# FabricationSumo.net
KiCad netlist of a schematic drawn in Altium Designer
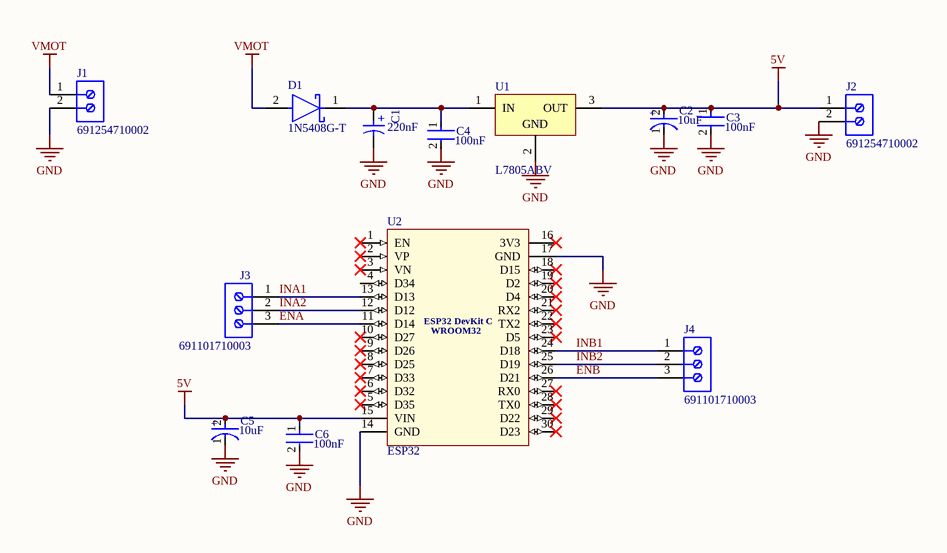
[diagram p0: FabricationSumo.SchDoc]

(export (version "E")
  (design (tool "Eeschema 10.0.6"))
  (components
    (comp (ref "C1")
      (value "860020672002")
      (footprint "WCAP-ATG5_D5H11")
      (description "WCAP-ATG5 Aluminum Electrolytic Capacitors")
      (fields (field (name "TOLERANCE") "20%") (field (name "CAPACITANCE") "220nF"))
      (libsource (lib "Altium Content Vault") (part "Capacitor_Polarized"))
    )
    (comp (ref "C2")
      (value "EEAGA1E100E")
      (footprint "FP-RAD-TH-D_4_0_5-L_7_1-F-MFG")
      (description "Aluminum Electrolytic Capacitors (Radial Lead Type) 10uF ±20% 25V")
      (fields (field (name "CAPACITANCE") "10uF"))
      (libsource (lib "Altium Content Vault") (part "a00bbbee19879c290e62620ae7e47b1"))
    )
    (comp (ref "C3")
      (value "RDED72W104K3K1H03B")
      (footprint "FP-RDE3M1-MFG")
      (description "Ceramic Capacitor 100nF ±10% 450V X7T Radial")
      (fields (field (name "TOLERANCE") "10%") (field (name "CAPACITANCE") "100nF"))
      (libsource (lib "Altium Content Vault") (part "b4654b650e69147ec39a6b967a45e02"))
    )
    (comp (ref "C4")
      (value "RDED72W104K3K1H03B")
      (footprint "FP-RDE3M1-MFG")
      (description "Ceramic Capacitor 100nF ±10% 450V X7T Radial")
      (fields (field (name "TOLERANCE") "10%") (field (name "CAPACITANCE") "100nF"))
      (libsource (lib "Altium Content Vault") (part "b4654b650e69147ec39a6b967a45e02"))
    )
    (comp (ref "C5")
      (value "EEAGA1E100E")
      (footprint "FP-RAD-TH-D_4_0_5-L_7_1-F-MFG")
      (description "Aluminum Electrolytic Capacitors (Radial Lead Type) 10uF ±20% 25V")
      (fields (field (name "CAPACITANCE") "10uF"))
      (libsource (lib "Altium Content Vault") (part "a00bbbee19879c290e62620ae7e47b1"))
    )
    (comp (ref "C6")
      (value "RDED72W104K3K1H03B")
      (footprint "FP-RDE3M1-MFG")
      (description "Ceramic Capacitor 100nF ±10% 450V X7T Radial")
      (fields (field (name "TOLERANCE") "10%") (field (name "CAPACITANCE") "100nF"))
      (libsource (lib "Altium Content Vault") (part "b4654b650e69147ec39a6b967a45e02"))
    )
    (comp (ref "D1")
      (value "1N5408G-T")
      (footprint "FP-DO-201AD-MFG")
      (description "Diode Schottky 40V 1A Through Hole DO-41")
      (fields (field (name "MANUFACTURER") "Diodes Inc."))
      (libsource (lib "Altium Content Vault") (part "1d6ec82d83fb6aee721767c19dac4b9"))
    )
    (comp (ref "J1")
      (value "691254710002")
      (footprint "691254710002")
      (description "Terminal Block, 5MM Pitch, Horizontal, Rising Cage Clamp, 16-30 AWG, 2 Pin")
      (libsource (lib "Altium Content Vault") (part "TBL - 1R - 02P - Screw"))
    )
    (comp (ref "J2")
      (value "691254710002")
      (footprint "691254710002")
      (description "Terminal Block, 5MM Pitch, Horizontal, Rising Cage Clamp, 16-30 AWG, 2 Pin")
      (libsource (lib "Altium Content Vault") (part "TBL - 1R - 02P - Screw"))
    )
    (comp (ref "J3")
      (value "691101710003")
      (footprint "691101710003")
      (description "101 Series 5MM Pitch Straight, Pcb Terminal Block, Through Hole, 3 Way")
      (fields (field (name "VOLTAGE") "250V"))
      (libsource (lib "Altium Content Vault") (part "TBL - 1R - 03P - Screw"))
    )
    (comp (ref "J4")
      (value "691101710003")
      (footprint "691101710003")
      (description "101 Series 5MM Pitch Straight, Pcb Terminal Block, Through Hole, 3 Way")
      (fields (field (name "VOLTAGE") "250V"))
      (libsource (lib "Altium Content Vault") (part "TBL - 1R - 03P - Screw"))
    )
    (comp (ref "U1")
      (value "L7805ABV")
      (footprint "TO220")
      (description "Positive Voltage Regulator, 5V, 3-Pin TO-220")
      (libsource (lib "Altium Content Vault") (part "PM-REG-L4940-SIL3"))
    )
    (comp (ref "U2")
      (value "ESP32")
      (footprint "ESP32_DevKitCWROOM32")
      (description "Multiprotocol Modules SMD Module ESP32-WROOM-32E, ESP32-D0WD-V3, 16 MB SPI flash, PCB antenna")
      (fields
        (field (name "MANUFACTURER") "Espressif Systems")
        (field (name "MANUFACTURER PART NUMBER") "ESP32-WROOM-32E-N16")
      )
      (libsource (lib "EspressifSystems") (part "ESP32-WROOM32"))
    )
  )
  (nets
    (net (code "1") (name "/ENA") (class "Default")
      (node (ref "J3") (pin "3") (pinfunction "3_3") (pintype "passive"))
      (node (ref "U2") (pin "11") (pinfunction "D14_11") (pintype "bidirectional"))
    )
    (net (code "2") (name "/ENB") (class "Default")
      (node (ref "J4") (pin "3") (pinfunction "3_3") (pintype "passive"))
      (node (ref "U2") (pin "26") (pinfunction "D21_26") (pintype "bidirectional"))
    )
    (net (code "3") (name "/INA1") (class "Default")
      (node (ref "J3") (pin "1") (pinfunction "1_1") (pintype "passive"))
      (node (ref "U2") (pin "13") (pinfunction "D13_13") (pintype "bidirectional"))
    )
    (net (code "4") (name "/INA2") (class "Default")
      (node (ref "J3") (pin "2") (pinfunction "2_2") (pintype "passive"))
      (node (ref "U2") (pin "12") (pinfunction "D12_12") (pintype "bidirectional"))
    )
    (net (code "5") (name "/INB1") (class "Default")
      (node (ref "J4") (pin "1") (pinfunction "1_1") (pintype "passive"))
      (node (ref "U2") (pin "24") (pinfunction "D18_24") (pintype "bidirectional"))
    )
    (net (code "6") (name "/INB2") (class "Default")
      (node (ref "J4") (pin "2") (pinfunction "2_2") (pintype "passive"))
      (node (ref "U2") (pin "25") (pinfunction "D19_25") (pintype "bidirectional"))
    )
    (net (code "7") (name "5V") (class "Default")
      (node (ref "C2") (pin "2") (pinfunction "A_2") (pintype "passive"))
      (node (ref "C3") (pin "1") (pinfunction "1_1") (pintype "passive"))
      (node (ref "C5") (pin "2") (pinfunction "A_2") (pintype "passive"))
      (node (ref "C6") (pin "1") (pinfunction "1_1") (pintype "passive"))
      (node (ref "J2") (pin "1") (pinfunction "1_1") (pintype "passive"))
      (node (ref "U1") (pin "3") (pinfunction "OUT_3") (pintype "power_in"))
      (node (ref "U2") (pin "15") (pinfunction "VIN_15") (pintype "power_in"))
    )
    (net (code "8") (name "GND") (class "Default")
      (node (ref "C1") (pin "2") (pinfunction "N_2") (pintype "passive"))
      (node (ref "C2") (pin "1") (pinfunction "C_1") (pintype "passive"))
      (node (ref "C3") (pin "2") (pinfunction "2_2") (pintype "passive"))
      (node (ref "C4") (pin "2") (pinfunction "2_2") (pintype "passive"))
      (node (ref "C5") (pin "1") (pinfunction "C_1") (pintype "passive"))
      (node (ref "C6") (pin "2") (pinfunction "2_2") (pintype "passive"))
      (node (ref "J1") (pin "2") (pinfunction "2_2") (pintype "passive"))
      (node (ref "J2") (pin "2") (pinfunction "2_2") (pintype "passive"))
      (node (ref "U1") (pin "2") (pinfunction "GND_2") (pintype "power_in"))
      (node (ref "U2") (pin "14") (pinfunction "GND_14") (pintype "power_in"))
      (node (ref "U2") (pin "17") (pinfunction "GND_17") (pintype "power_in"))
    )
    (net (code "9") (name "Net-(C1-P)") (class "Default")
      (node (ref "C1") (pin "1") (pinfunction "P_1") (pintype "passive"))
      (node (ref "C4") (pin "1") (pinfunction "1_1") (pintype "passive"))
      (node (ref "D1") (pin "1") (pinfunction "C_1") (pintype "passive"))
      (node (ref "U1") (pin "1") (pinfunction "IN_1") (pintype "power_in"))
    )
    (net (code "10") (name "VMOT") (class "Default")
      (node (ref "D1") (pin "2") (pinfunction "A_2") (pintype "passive"))
      (node (ref "J1") (pin "1") (pinfunction "1_1") (pintype "passive"))
    )
    (net (code "11") (name "unconnected-(U2-3V3-Pad16)") (class "Default")
      (node (ref "U2") (pin "16") (pinfunction "3V3_16") (pintype "power_in+no_connect"))
    )
    (net (code "12") (name "unconnected-(U2-D2-Pad19)") (class "Default")
      (node (ref "U2") (pin "19") (pinfunction "D2_19") (pintype "bidirectional+no_connect"))
    )
    (net (code "13") (name "unconnected-(U2-D4-Pad20)") (class "Default")
      (node (ref "U2") (pin "20") (pinfunction "D4_20") (pintype "bidirectional+no_connect"))
    )
    (net (code "14") (name "unconnected-(U2-D5-Pad23)") (class "Default")
      (node (ref "U2") (pin "23") (pinfunction "D5_23") (pintype "bidirectional+no_connect"))
    )
    (net (code "15") (name "unconnected-(U2-D15-Pad18)") (class "Default")
      (node (ref "U2") (pin "18") (pinfunction "D15_18") (pintype "bidirectional+no_connect"))
    )
    (net (code "16") (name "unconnected-(U2-D22-Pad29)") (class "Default")
      (node (ref "U2") (pin "29") (pinfunction "D22_29") (pintype "bidirectional+no_connect"))
    )
    (net (code "17") (name "unconnected-(U2-D23-Pad30)") (class "Default")
      (node (ref "U2") (pin "30") (pinfunction "D23_30") (pintype "bidirectional+no_connect"))
    )
    (net (code "18") (name "unconnected-(U2-D25-Pad8)") (class "Default")
      (node (ref "U2") (pin "8") (pinfunction "D25_8") (pintype "bidirectional+no_connect"))
    )
    (net (code "19") (name "unconnected-(U2-D26-Pad9)") (class "Default")
      (node (ref "U2") (pin "9") (pinfunction "D26_9") (pintype "bidirectional+no_connect"))
    )
    (net (code "20") (name "unconnected-(U2-D27-Pad10)") (class "Default")
      (node (ref "U2") (pin "10") (pinfunction "D27_10") (pintype "bidirectional+no_connect"))
    )
    (net (code "21") (name "unconnected-(U2-D32-Pad6)") (class "Default")
      (node (ref "U2") (pin "6") (pinfunction "D32_6") (pintype "bidirectional+no_connect"))
    )
    (net (code "22") (name "unconnected-(U2-D33-Pad7)") (class "Default")
      (node (ref "U2") (pin "7") (pinfunction "D33_7") (pintype "bidirectional+no_connect"))
    )
    (net (code "23") (name "unconnected-(U2-D34-Pad4)") (class "Default")
      (node (ref "U2") (pin "4") (pinfunction "D34_4") (pintype "bidirectional"))
    )
    (net (code "24") (name "unconnected-(U2-D35-Pad5)") (class "Default")
      (node (ref "U2") (pin "5") (pinfunction "D35_5") (pintype "bidirectional+no_connect"))
    )
    (net (code "25") (name "unconnected-(U2-EN-Pad1)") (class "Default")
      (node (ref "U2") (pin "1") (pinfunction "EN_1") (pintype "input+no_connect"))
    )
    (net (code "26") (name "unconnected-(U2-RX0-Pad27)") (class "Default")
      (node (ref "U2") (pin "27") (pinfunction "RX0_27") (pintype "bidirectional+no_connect"))
    )
    (net (code "27") (name "unconnected-(U2-RX2-Pad21)") (class "Default")
      (node (ref "U2") (pin "21") (pinfunction "RX2_21") (pintype "bidirectional+no_connect"))
    )
    (net (code "28") (name "unconnected-(U2-TX0-Pad28)") (class "Default")
      (node (ref "U2") (pin "28") (pinfunction "TX0_28") (pintype "bidirectional+no_connect"))
    )
    (net (code "29") (name "unconnected-(U2-TX2-Pad22)") (class "Default")
      (node (ref "U2") (pin "22") (pinfunction "TX2_22") (pintype "bidirectional+no_connect"))
    )
    (net (code "30") (name "unconnected-(U2-VN-Pad3)") (class "Default")
      (node (ref "U2") (pin "3") (pinfunction "VN_3") (pintype "input+no_connect"))
    )
    (net (code "31") (name "unconnected-(U2-VP-Pad2)") (class "Default")
      (node (ref "U2") (pin "2") (pinfunction "VP_2") (pintype "input+no_connect"))
    )
  )
)
